# SCH_TRSID_2026-05-15.net
KiCad netlist of a schematic drawn in EasyEDA
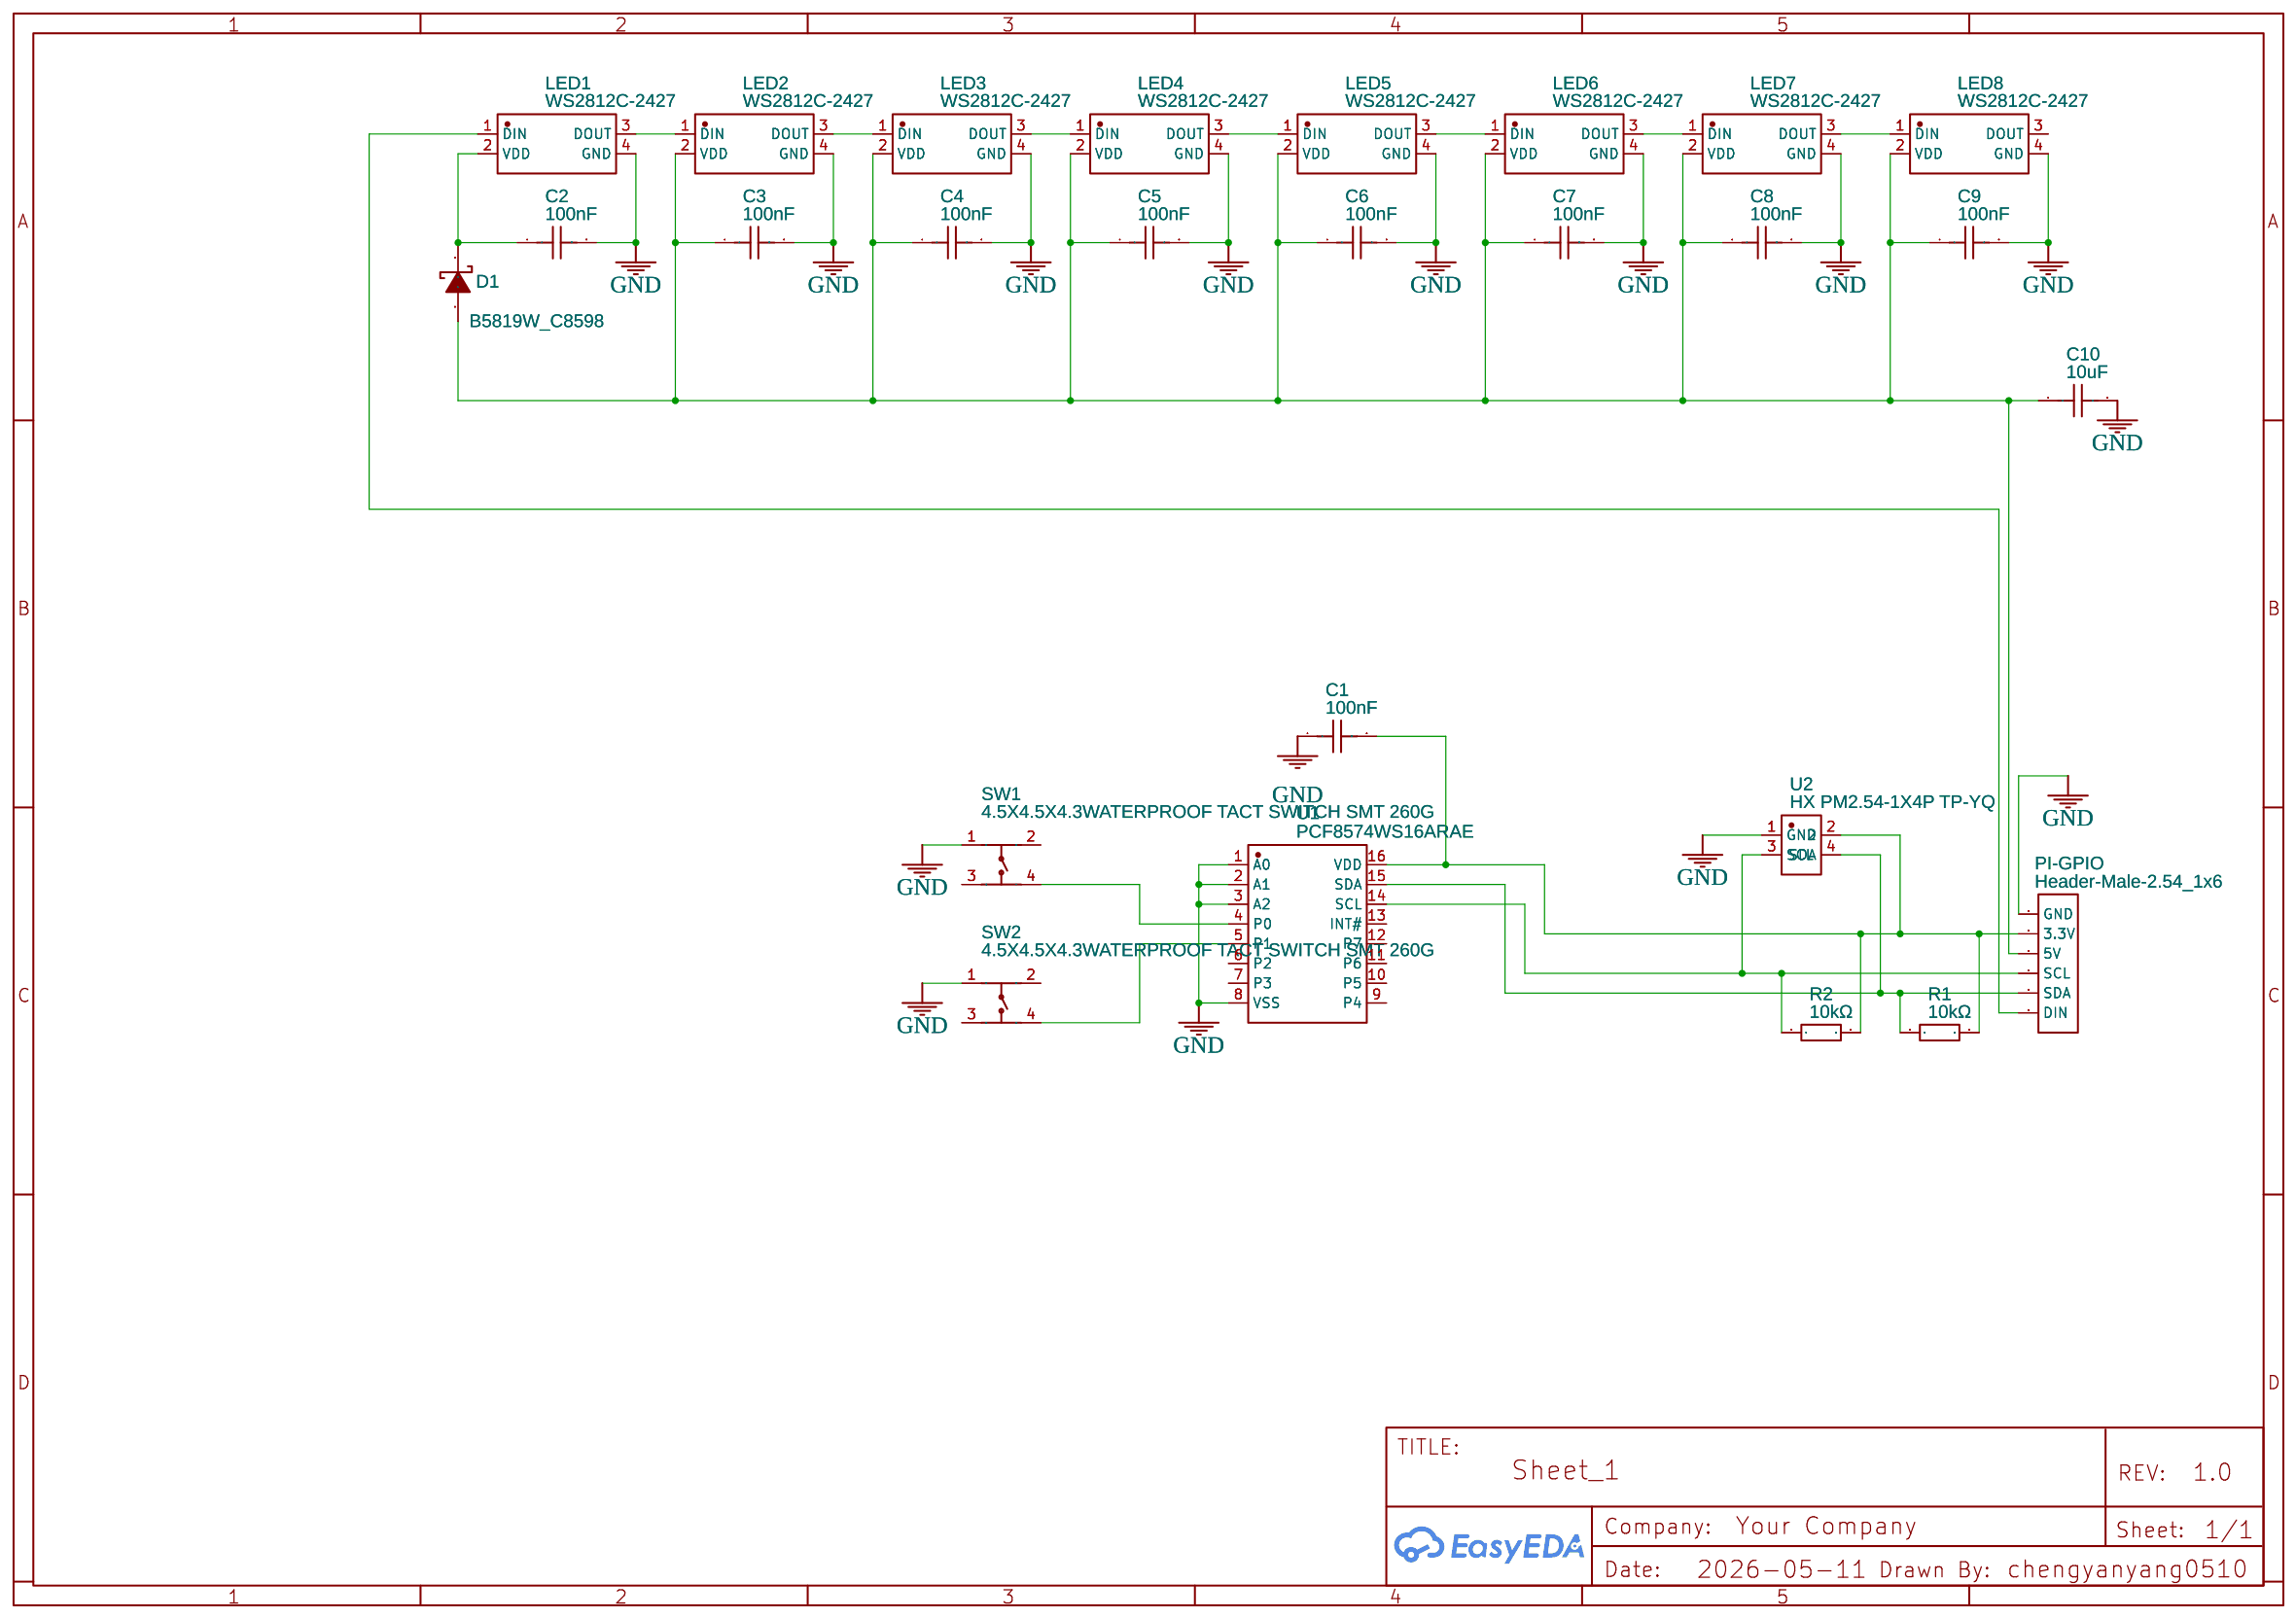
[diagram p0: schematic sheet]

(export (version "E")
  (design (tool "Eeschema 10.0.6"))
  (components
    (comp (ref "C1")
      (value "100nF")
      (fields
        (field (name "Manufacturer Part") "CL05B104KO5NNNC")
        (field (name "Manufacturer") "SAMSUNG(三星)")
      )
      (libsource (lib "") (part "CL05B104KO5NNNC"))
    )
    (comp (ref "C2")
      (value "100nF")
      (fields
        (field (name "Manufacturer Part") "CL05B104KO5NNNC")
        (field (name "Manufacturer") "SAMSUNG(三星)")
      )
      (libsource (lib "") (part "CL05B104KO5NNNC"))
    )
    (comp (ref "C3")
      (value "100nF")
      (fields
        (field (name "Manufacturer Part") "CL05B104KO5NNNC")
        (field (name "Manufacturer") "SAMSUNG(三星)")
      )
      (libsource (lib "") (part "CL05B104KO5NNNC"))
    )
    (comp (ref "C4")
      (value "100nF")
      (fields
        (field (name "Manufacturer Part") "CL05B104KO5NNNC")
        (field (name "Manufacturer") "SAMSUNG(三星)")
      )
      (libsource (lib "") (part "CL05B104KO5NNNC"))
    )
    (comp (ref "C5")
      (value "100nF")
      (fields
        (field (name "Manufacturer Part") "CL05B104KO5NNNC")
        (field (name "Manufacturer") "SAMSUNG(三星)")
      )
      (libsource (lib "") (part "CL05B104KO5NNNC"))
    )
    (comp (ref "C6")
      (value "100nF")
      (fields
        (field (name "Manufacturer Part") "CL05B104KO5NNNC")
        (field (name "Manufacturer") "SAMSUNG(三星)")
      )
      (libsource (lib "") (part "CL05B104KO5NNNC"))
    )
    (comp (ref "C7")
      (value "100nF")
      (fields
        (field (name "Manufacturer Part") "CL05B104KO5NNNC")
        (field (name "Manufacturer") "SAMSUNG(三星)")
      )
      (libsource (lib "") (part "CL05B104KO5NNNC"))
    )
    (comp (ref "C8")
      (value "100nF")
      (fields
        (field (name "Manufacturer Part") "CL05B104KO5NNNC")
        (field (name "Manufacturer") "SAMSUNG(三星)")
      )
      (libsource (lib "") (part "CL05B104KO5NNNC"))
    )
    (comp (ref "C9")
      (value "100nF")
      (fields
        (field (name "Manufacturer Part") "CL05B104KO5NNNC")
        (field (name "Manufacturer") "SAMSUNG(三星)")
      )
      (libsource (lib "") (part "CL05B104KO5NNNC"))
    )
    (comp (ref "C10")
      (value "10uF")
      (fields
        (field (name "Manufacturer Part") "CL10A106KP8NNNC")
        (field (name "Manufacturer") "SAMSUNG(三星)")
      )
      (libsource (lib "") (part "CL10A106KP8NNNC"))
    )
    (comp (ref "D1")
      (value "B5819W_C8598")
      (fields (field (name "Manufacturer Part") "B5819W SL") (field (name "Manufacturer") "CJ(江苏长电/长晶)"))
      (libsource (lib "") (part "B5819W_C8598"))
    )
    (comp (ref "LED1")
      (value "WS2812C-2427")
      (fields (field (name "Manufacturer") "worldsemi"))
      (libsource (lib "") (part "WS2812C-2427"))
    )
    (comp (ref "LED2")
      (value "WS2812C-2427")
      (fields (field (name "Manufacturer") "worldsemi"))
      (libsource (lib "") (part "WS2812C-2427"))
    )
    (comp (ref "LED3")
      (value "WS2812C-2427")
      (fields (field (name "Manufacturer") "worldsemi"))
      (libsource (lib "") (part "WS2812C-2427"))
    )
    (comp (ref "LED4")
      (value "WS2812C-2427")
      (fields (field (name "Manufacturer") "worldsemi"))
      (libsource (lib "") (part "WS2812C-2427"))
    )
    (comp (ref "LED5")
      (value "WS2812C-2427")
      (fields (field (name "Manufacturer") "worldsemi"))
      (libsource (lib "") (part "WS2812C-2427"))
    )
    (comp (ref "LED6")
      (value "WS2812C-2427")
      (fields (field (name "Manufacturer") "worldsemi"))
      (libsource (lib "") (part "WS2812C-2427"))
    )
    (comp (ref "LED7")
      (value "WS2812C-2427")
      (fields (field (name "Manufacturer") "worldsemi"))
      (libsource (lib "") (part "WS2812C-2427"))
    )
    (comp (ref "LED8")
      (value "WS2812C-2427")
      (fields (field (name "Manufacturer") "worldsemi"))
      (libsource (lib "") (part "WS2812C-2427"))
    )
    (comp (ref "PI-GPIO")
      (value "Header-Male-2.54_1x6")
      (fields (field (name "Manufacturer Part") "2.54-1x6P直针") (field (name "Manufacturer") "BOOMELE(博穆精密)"))
      (libsource (lib "") (part "Header-Male-2.54_1x6"))
    )
    (comp (ref "R1")
      (value "10kΩ")
      (fields
        (field (name "Manufacturer Part") "1206W4F1002T5E")
        (field (name "Manufacturer") "UNI-ROYAL(厚声)")
      )
      (libsource (lib "") (part "1206W4F1002T5E"))
    )
    (comp (ref "R2")
      (value "10kΩ")
      (fields
        (field (name "Manufacturer Part") "1206W4F1002T5E")
        (field (name "Manufacturer") "UNI-ROYAL(厚声)")
      )
      (libsource (lib "") (part "1206W4F1002T5E"))
    )
    (comp (ref "SW1")
      (value "4.5X4.5X4.3WATERPROOF TACT SWITCH SMT 260G")
      (fields
        (field (name "Manufacturer Part") "4.5x4.5x4.3Waterproof Tact Switch SMT 260g")
        (field (name "Manufacturer") "CAX(创都)")
      )
      (libsource (lib "") (part "4.5X4.5X4.3WATERPROOF TACT SWITCH SMT 260G"))
    )
    (comp (ref "SW2")
      (value "4.5X4.5X4.3WATERPROOF TACT SWITCH SMT 260G")
      (fields
        (field (name "Manufacturer Part") "4.5x4.5x4.3Waterproof Tact Switch SMT 260g")
        (field (name "Manufacturer") "CAX(创都)")
      )
      (libsource (lib "") (part "4.5X4.5X4.3WATERPROOF TACT SWITCH SMT 260G"))
    )
    (comp (ref "U1")
      (value "PCF8574WS16ARAE")
      (fields (field (name "Manufacturer") "GR(国睿)"))
      (libsource (lib "") (part "PCF8574WS16ARAE"))
    )
    (comp (ref "U2")
      (value "HX PM2.54-1X4P TP-YQ")
      (fields
        (field (name "Manufacturer Part") "HX PM2.54-1x4P TP-YQ")
        (field (name "Manufacturer") "hanxia(韩下)")
      )
      (libsource (lib "") (part "HX PM2.54-1X4P TP-YQ"))
    )
  )
  (nets
    (net (code "1") (name "GND") (class "Default")
      (node (ref "C1") (pin "1") (pinfunction "1_1") (pintype "unspecified"))
      (node (ref "C10") (pin "2") (pinfunction "2_2") (pintype "unspecified"))
      (node (ref "C2") (pin "2") (pinfunction "2_2") (pintype "unspecified"))
      (node (ref "C3") (pin "2") (pinfunction "2_2") (pintype "unspecified"))
      (node (ref "C4") (pin "2") (pinfunction "2_2") (pintype "unspecified"))
      (node (ref "C5") (pin "2") (pinfunction "2_2") (pintype "unspecified"))
      (node (ref "C6") (pin "2") (pinfunction "2_2") (pintype "unspecified"))
      (node (ref "C7") (pin "2") (pinfunction "2_2") (pintype "unspecified"))
      (node (ref "C8") (pin "2") (pinfunction "2_2") (pintype "unspecified"))
      (node (ref "C9") (pin "2") (pinfunction "2_2") (pintype "unspecified"))
      (node (ref "LED1") (pin "4") (pinfunction "GND_4") (pintype "unspecified"))
      (node (ref "LED2") (pin "4") (pinfunction "GND_4") (pintype "unspecified"))
      (node (ref "LED3") (pin "4") (pinfunction "GND_4") (pintype "unspecified"))
      (node (ref "LED4") (pin "4") (pinfunction "GND_4") (pintype "unspecified"))
      (node (ref "LED5") (pin "4") (pinfunction "GND_4") (pintype "unspecified"))
      (node (ref "LED6") (pin "4") (pinfunction "GND_4") (pintype "unspecified"))
      (node (ref "LED7") (pin "4") (pinfunction "GND_4") (pintype "unspecified"))
      (node (ref "LED8") (pin "4") (pinfunction "GND_4") (pintype "unspecified"))
      (node (ref "PI-GPIO") (pin "1") (pinfunction "GND_1") (pintype "input"))
      (node (ref "SW1") (pin "1") (pinfunction "1_1") (pintype "unspecified"))
      (node (ref "SW2") (pin "1") (pinfunction "1_1") (pintype "unspecified"))
      (node (ref "U1") (pin "1") (pinfunction "A0_1") (pintype "unspecified"))
      (node (ref "U1") (pin "2") (pinfunction "A1_2") (pintype "unspecified"))
      (node (ref "U1") (pin "3") (pinfunction "A2_3") (pintype "unspecified"))
      (node (ref "U1") (pin "8") (pinfunction "VSS_8") (pintype "unspecified"))
      (node (ref "U2") (pin "1") (pinfunction "GND_1") (pintype "unspecified"))
    )
    (net (code "2") (name "Net-(D1-+)") (class "Default")
      (node (ref "C10") (pin "1") (pinfunction "1_1") (pintype "unspecified"))
      (node (ref "C3") (pin "1") (pinfunction "1_1") (pintype "unspecified"))
      (node (ref "C4") (pin "1") (pinfunction "1_1") (pintype "unspecified"))
      (node (ref "C5") (pin "1") (pinfunction "1_1") (pintype "unspecified"))
      (node (ref "C6") (pin "1") (pinfunction "1_1") (pintype "unspecified"))
      (node (ref "C7") (pin "1") (pinfunction "1_1") (pintype "unspecified"))
      (node (ref "C8") (pin "1") (pinfunction "1_1") (pintype "unspecified"))
      (node (ref "C9") (pin "1") (pinfunction "1_1") (pintype "unspecified"))
      (node (ref "D1") (pin "2") (pinfunction "+_2") (pintype "unspecified"))
      (node (ref "LED2") (pin "2") (pinfunction "VDD_2") (pintype "unspecified"))
      (node (ref "LED3") (pin "2") (pinfunction "VDD_2") (pintype "unspecified"))
      (node (ref "LED4") (pin "2") (pinfunction "VDD_2") (pintype "unspecified"))
      (node (ref "LED5") (pin "2") (pinfunction "VDD_2") (pintype "unspecified"))
      (node (ref "LED6") (pin "2") (pinfunction "VDD_2") (pintype "unspecified"))
      (node (ref "LED7") (pin "2") (pinfunction "VDD_2") (pintype "unspecified"))
      (node (ref "LED8") (pin "2") (pinfunction "VDD_2") (pintype "unspecified"))
      (node (ref "PI-GPIO") (pin "3") (pinfunction "5V_3") (pintype "input"))
    )
    (net (code "3") (name "Net-(D1--)") (class "Default")
      (node (ref "C2") (pin "1") (pinfunction "1_1") (pintype "unspecified"))
      (node (ref "D1") (pin "1") (pinfunction "-_1") (pintype "unspecified"))
      (node (ref "LED1") (pin "2") (pinfunction "VDD_2") (pintype "unspecified"))
    )
    (net (code "4") (name "Net-(LED1-DIN)") (class "Default")
      (node (ref "LED1") (pin "1") (pinfunction "DIN_1") (pintype "unspecified"))
      (node (ref "PI-GPIO") (pin "6") (pinfunction "DIN_6") (pintype "input"))
    )
    (net (code "5") (name "Net-(LED1-DOUT)") (class "Default")
      (node (ref "LED1") (pin "3") (pinfunction "DOUT_3") (pintype "unspecified"))
      (node (ref "LED2") (pin "1") (pinfunction "DIN_1") (pintype "unspecified"))
    )
    (net (code "6") (name "Net-(LED2-DOUT)") (class "Default")
      (node (ref "LED2") (pin "3") (pinfunction "DOUT_3") (pintype "unspecified"))
      (node (ref "LED3") (pin "1") (pinfunction "DIN_1") (pintype "unspecified"))
    )
    (net (code "7") (name "Net-(LED3-DOUT)") (class "Default")
      (node (ref "LED3") (pin "3") (pinfunction "DOUT_3") (pintype "unspecified"))
      (node (ref "LED4") (pin "1") (pinfunction "DIN_1") (pintype "unspecified"))
    )
    (net (code "8") (name "Net-(LED4-DOUT)") (class "Default")
      (node (ref "LED4") (pin "3") (pinfunction "DOUT_3") (pintype "unspecified"))
      (node (ref "LED5") (pin "1") (pinfunction "DIN_1") (pintype "unspecified"))
    )
    (net (code "9") (name "Net-(LED5-DOUT)") (class "Default")
      (node (ref "LED5") (pin "3") (pinfunction "DOUT_3") (pintype "unspecified"))
      (node (ref "LED6") (pin "1") (pinfunction "DIN_1") (pintype "unspecified"))
    )
    (net (code "10") (name "Net-(LED6-DOUT)") (class "Default")
      (node (ref "LED6") (pin "3") (pinfunction "DOUT_3") (pintype "unspecified"))
      (node (ref "LED7") (pin "1") (pinfunction "DIN_1") (pintype "unspecified"))
    )
    (net (code "11") (name "Net-(LED7-DOUT)") (class "Default")
      (node (ref "LED7") (pin "3") (pinfunction "DOUT_3") (pintype "unspecified"))
      (node (ref "LED8") (pin "1") (pinfunction "DIN_1") (pintype "unspecified"))
    )
    (net (code "12") (name "Net-(PI-GPIO-3.3V)") (class "Default")
      (node (ref "C1") (pin "2") (pinfunction "2_2") (pintype "unspecified"))
      (node (ref "PI-GPIO") (pin "2") (pinfunction "3.3V_2") (pintype "input"))
      (node (ref "R1") (pin "2") (pinfunction "2_2") (pintype "input"))
      (node (ref "R2") (pin "2") (pinfunction "2_2") (pintype "input"))
      (node (ref "U1") (pin "16") (pinfunction "VDD_16") (pintype "unspecified"))
      (node (ref "U2") (pin "2") (pinfunction "2_2") (pintype "unspecified"))
    )
    (net (code "13") (name "Net-(PI-GPIO-SCL)") (class "Default")
      (node (ref "PI-GPIO") (pin "4") (pinfunction "SCL_4") (pintype "input"))
      (node (ref "R2") (pin "1") (pinfunction "1_1") (pintype "input"))
      (node (ref "U1") (pin "14") (pinfunction "SCL_14") (pintype "unspecified"))
      (node (ref "U2") (pin "3") (pinfunction "SCL_3") (pintype "unspecified"))
    )
    (net (code "14") (name "Net-(PI-GPIO-SDA)") (class "Default")
      (node (ref "PI-GPIO") (pin "5") (pinfunction "SDA_5") (pintype "input"))
      (node (ref "R1") (pin "1") (pinfunction "1_1") (pintype "input"))
      (node (ref "U1") (pin "15") (pinfunction "SDA_15") (pintype "unspecified"))
      (node (ref "U2") (pin "4") (pinfunction "SDA_4") (pintype "unspecified"))
    )
    (net (code "15") (name "Net-(U1-P0)") (class "Default")
      (node (ref "SW1") (pin "4") (pinfunction "4_4") (pintype "unspecified"))
      (node (ref "U1") (pin "4") (pinfunction "P0_4") (pintype "unspecified"))
    )
    (net (code "16") (name "Net-(U1-P1)") (class "Default")
      (node (ref "SW2") (pin "4") (pinfunction "4_4") (pintype "unspecified"))
      (node (ref "U1") (pin "5") (pinfunction "P1_5") (pintype "unspecified"))
    )
    (net (code "17") (name "unconnected-(LED8-DOUT-Pad3)") (class "Default")
      (node (ref "LED8") (pin "3") (pinfunction "DOUT_3") (pintype "unspecified"))
    )
    (net (code "18") (name "unconnected-(SW1-Pad2)") (class "Default")
      (node (ref "SW1") (pin "2") (pinfunction "2_2") (pintype "unspecified"))
    )
    (net (code "19") (name "unconnected-(SW1-Pad3)") (class "Default")
      (node (ref "SW1") (pin "3") (pinfunction "3_3") (pintype "unspecified"))
    )
    (net (code "20") (name "unconnected-(SW2-Pad2)") (class "Default")
      (node (ref "SW2") (pin "2") (pinfunction "2_2") (pintype "unspecified"))
    )
    (net (code "21") (name "unconnected-(SW2-Pad3)") (class "Default")
      (node (ref "SW2") (pin "3") (pinfunction "3_3") (pintype "unspecified"))
    )
    (net (code "22") (name "unconnected-(U1-INT#-Pad13)") (class "Default")
      (node (ref "U1") (pin "13") (pinfunction "INT#_13") (pintype "unspecified"))
    )
    (net (code "23") (name "unconnected-(U1-P2-Pad6)") (class "Default")
      (node (ref "U1") (pin "6") (pinfunction "P2_6") (pintype "unspecified"))
    )
    (net (code "24") (name "unconnected-(U1-P3-Pad7)") (class "Default")
      (node (ref "U1") (pin "7") (pinfunction "P3_7") (pintype "unspecified"))
    )
    (net (code "25") (name "unconnected-(U1-P4-Pad9)") (class "Default")
      (node (ref "U1") (pin "9") (pinfunction "P4_9") (pintype "unspecified"))
    )
    (net (code "26") (name "unconnected-(U1-P5-Pad10)") (class "Default")
      (node (ref "U1") (pin "10") (pinfunction "P5_10") (pintype "unspecified"))
    )
    (net (code "27") (name "unconnected-(U1-P6-Pad11)") (class "Default")
      (node (ref "U1") (pin "11") (pinfunction "P6_11") (pintype "unspecified"))
    )
    (net (code "28") (name "unconnected-(U1-P7-Pad12)") (class "Default")
      (node (ref "U1") (pin "12") (pinfunction "P7_12") (pintype "unspecified"))
    )
  )
)
